# lab_1_demcheva_usb_rs232.net
KiCad netlist of a schematic drawn in Altium Designer
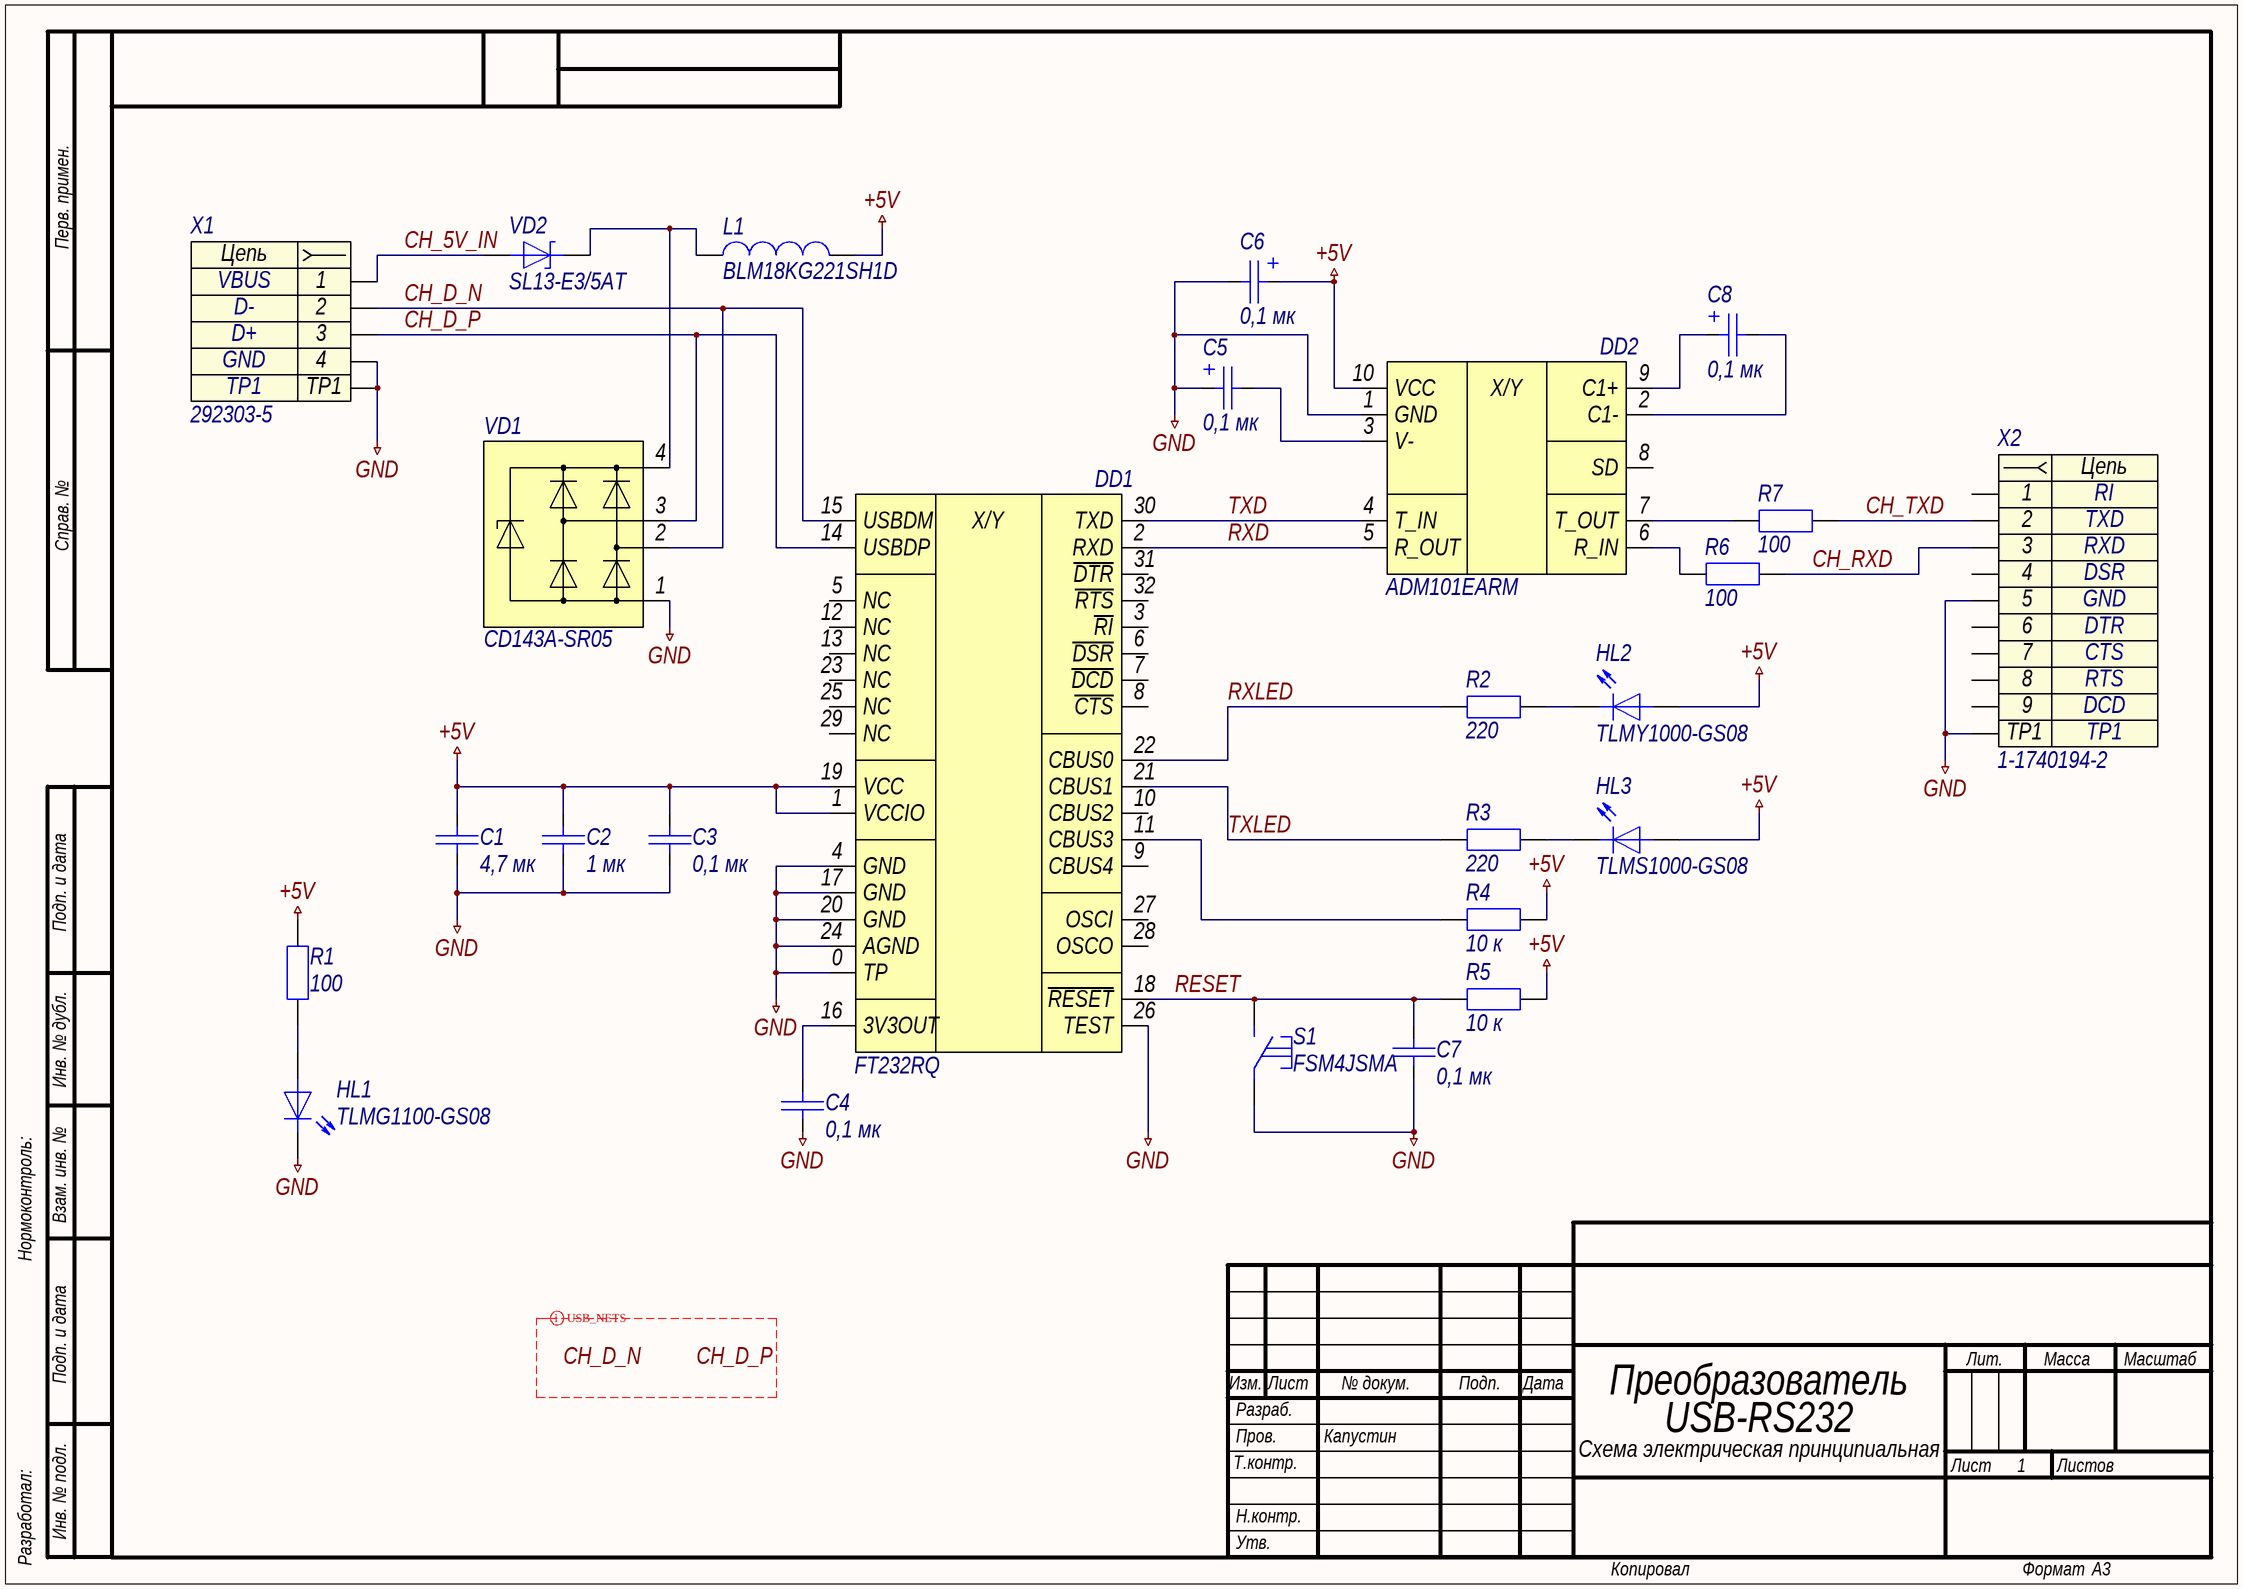
[diagram p0: lab_1_demcheva_usb_rs232.SchDoc]

(export (version "E")
  (design (tool "Eeschema 10.0.6"))
  (components
    (comp (ref "C1")
      (value "4,7 мк")
      (footprint "C0603")
      (description "=Описание")
      (libsource (lib "Database_Students") (part "C-NONPOLAR"))
    )
    (comp (ref "C2")
      (value "1 мк")
      (footprint "C0603")
      (description "=Описание")
      (libsource (lib "Database_Students") (part "C-NONPOLAR"))
    )
    (comp (ref "C3")
      (value "0,1 мк")
      (footprint "C0603")
      (description "=Описание")
      (libsource (lib "Database_Students") (part "C-NONPOLAR"))
    )
    (comp (ref "C4")
      (value "0,1 мк")
      (footprint "C0603")
      (description "=Описание")
      (libsource (lib "Database_Students") (part "C-NONPOLAR"))
    )
    (comp (ref "C5")
      (value "0,1 мк")
      (footprint "C1206POLAR")
      (description "=Описание")
      (libsource (lib "Database_Students") (part "C-POLAR"))
    )
    (comp (ref "C6")
      (value "0,1 мк")
      (footprint "C1206POLAR")
      (description "=Описание")
      (libsource (lib "Database_Students") (part "C-POLAR"))
    )
    (comp (ref "C7")
      (value "0,1 мк")
      (footprint "C0603")
      (description "=Описание")
      (libsource (lib "Database_Students") (part "C-NONPOLAR"))
    )
    (comp (ref "C8")
      (value "0,1 мк")
      (footprint "C1206POLAR")
      (description "=Описание")
      (libsource (lib "Database_Students") (part "C-POLAR"))
    )
    (comp (ref "DD1")
      (value "FT232RQ")
      (footprint "QFN-32-500x500x90")
      (description "=Описание")
      (libsource (lib "Database_Students") (part "FT232RQ"))
    )
    (comp (ref "DD2")
      (value "ADM101EARM")
      (footprint "MSOP-10")
      (description "=Описание")
      (libsource (lib "Database_Students") (part "ADM101EARM"))
    )
    (comp (ref "HL1")
      (value "TLMG1100-GS08")
      (footprint "HL0603")
      (description "=Описание")
      (libsource (lib "Database_Students") (part "HL-COMMON"))
    )
    (comp (ref "HL2")
      (value "TLMY1000-GS08")
      (footprint "HL0603")
      (description "=Описание")
      (libsource (lib "Database_Students") (part "HL-COMMON"))
    )
    (comp (ref "HL3")
      (value "TLMS1000-GS08")
      (footprint "HL0603")
      (description "=Описание")
      (libsource (lib "Database_Students") (part "HL-COMMON"))
    )
    (comp (ref "L1")
      (value "BLM18KG221SH1D")
      (footprint "BLM-2-0603")
      (description "=Описание")
      (libsource (lib "Database_Students") (part "FERRITE-BEAD"))
    )
    (comp (ref "R1")
      (value "100")
      (footprint "R0603")
      (description "=Описание")
      (libsource (lib "Database_Students") (part "R-COMMON"))
    )
    (comp (ref "R2")
      (value "220")
      (footprint "R0603")
      (description "=Описание")
      (libsource (lib "Database_Students") (part "R-COMMON"))
    )
    (comp (ref "R3")
      (value "220")
      (footprint "R0603")
      (description "=Описание")
      (libsource (lib "Database_Students") (part "R-COMMON"))
    )
    (comp (ref "R4")
      (value "10 к")
      (footprint "R0603")
      (description "=Описание")
      (libsource (lib "Database_Students") (part "R-COMMON"))
    )
    (comp (ref "R5")
      (value "10 к")
      (footprint "R0603")
      (description "=Описание")
      (libsource (lib "Database_Students") (part "R-COMMON"))
    )
    (comp (ref "R6")
      (value "100")
      (footprint "R0603")
      (description "=Описание")
      (libsource (lib "Database_Students") (part "R-COMMON"))
    )
    (comp (ref "R7")
      (value "100")
      (footprint "R0603")
      (description "=Описание")
      (libsource (lib "Database_Students") (part "R-COMMON"))
    )
    (comp (ref "S1")
      (value "FSM4JSMA")
      (footprint "FSM4JSMA")
      (description "=Описание")
      (libsource (lib "Database_Students") (part "SWITCH-01"))
    )
    (comp (ref "VD1")
      (value "CD143A-SR05")
      (footprint "SOT-143-4")
      (description "=Описание")
      (libsource (lib "Database_Students") (part "CD143A-SR05"))
    )
    (comp (ref "VD2")
      (value "SL13-E3/5AT")
      (footprint "DO-214AC")
      (description "=Описание")
      (libsource (lib "Database_Students") (part "DIODE-SCHOTTKY"))
    )
    (comp (ref "X1")
      (value "292303-5")
      (footprint "292303-5")
      (description "=Описание")
      (libsource (lib "Database_Students") (part "HEADER-4-TP1-SCT"))
    )
    (comp (ref "X2")
      (value "1-1740194-2")
      (footprint "1-1740194-2")
      (description "=Описание")
      (libsource (lib "Database_Students") (part "HEADER-9-TP1-SCT"))
    )
  )
  (nets
    (net (code "1") (name "+5V") (class "Default")
      (node (ref "C1") (pin "1") (pinfunction "1_1") (pintype "passive"))
      (node (ref "C2") (pin "1") (pinfunction "1_1") (pintype "passive"))
      (node (ref "C3") (pin "1") (pinfunction "1_1") (pintype "passive"))
      (node (ref "C6") (pin "1") (pinfunction "1_1") (pintype "passive"))
      (node (ref "DD1") (pin "1") (pinfunction "VCCIO_1") (pintype "passive"))
      (node (ref "DD1") (pin "19") (pinfunction "VCC_19") (pintype "passive"))
      (node (ref "DD2") (pin "10") (pinfunction "VCC_10") (pintype "passive"))
      (node (ref "HL2") (pin "2") (pinfunction "2_2") (pintype "passive"))
      (node (ref "HL3") (pin "2") (pinfunction "2_2") (pintype "passive"))
      (node (ref "L1") (pin "2") (pinfunction "2_2") (pintype "passive"))
      (node (ref "R1") (pin "2") (pinfunction "2_2") (pintype "passive"))
      (node (ref "R4") (pin "2") (pinfunction "2_2") (pintype "passive"))
      (node (ref "R5") (pin "2") (pinfunction "2_2") (pintype "passive"))
    )
    (net (code "2") (name "/CH_5V_IN") (class "Default")
      (node (ref "VD2") (pin "2") (pinfunction "2_2") (pintype "passive"))
      (node (ref "X1") (pin "1") (pinfunction "1_1") (pintype "passive"))
    )
    (net (code "3") (name "/CH_D_N") (class "Default")
      (node (ref "DD1") (pin "15") (pinfunction "USBDM_15") (pintype "passive"))
      (node (ref "VD1") (pin "2") (pinfunction "2_2") (pintype "passive"))
      (node (ref "X1") (pin "2") (pinfunction "2_2") (pintype "passive"))
    )
    (net (code "4") (name "/CH_D_P") (class "Default")
      (node (ref "DD1") (pin "14") (pinfunction "USBDP_14") (pintype "passive"))
      (node (ref "VD1") (pin "3") (pinfunction "3_3") (pintype "passive"))
      (node (ref "X1") (pin "3") (pinfunction "3_3") (pintype "passive"))
    )
    (net (code "5") (name "/CH_RXD") (class "Default")
      (node (ref "R6") (pin "2") (pinfunction "2_2") (pintype "passive"))
      (node (ref "X2") (pin "3") (pinfunction "3_3") (pintype "passive"))
    )
    (net (code "6") (name "/CH_TXD") (class "Default")
      (node (ref "R7") (pin "2") (pinfunction "2_2") (pintype "passive"))
      (node (ref "X2") (pin "2") (pinfunction "2_2") (pintype "passive"))
    )
    (net (code "7") (name "/RESET") (class "Default")
      (node (ref "C7") (pin "1") (pinfunction "1_1") (pintype "passive"))
      (node (ref "DD1") (pin "18") (pinfunction "~{RESET}_18") (pintype "passive"))
      (node (ref "R5") (pin "1") (pinfunction "1_1") (pintype "passive"))
      (node (ref "S1") (pin "2") (pinfunction "2_2") (pintype "passive"))
    )
    (net (code "8") (name "/RXD") (class "Default")
      (node (ref "DD1") (pin "2") (pinfunction "RXD_2") (pintype "passive"))
      (node (ref "DD2") (pin "5") (pinfunction "R_OUT_5") (pintype "passive"))
    )
    (net (code "9") (name "/RXLED") (class "Default")
      (node (ref "DD1") (pin "22") (pinfunction "CBUS0_22") (pintype "passive"))
      (node (ref "R2") (pin "1") (pinfunction "1_1") (pintype "passive"))
    )
    (net (code "10") (name "/TXD") (class "Default")
      (node (ref "DD1") (pin "30") (pinfunction "TXD_30") (pintype "passive"))
      (node (ref "DD2") (pin "4") (pinfunction "T_IN_4") (pintype "passive"))
    )
    (net (code "11") (name "/TXLED") (class "Default")
      (node (ref "DD1") (pin "21") (pinfunction "CBUS1_21") (pintype "passive"))
      (node (ref "R3") (pin "1") (pinfunction "1_1") (pintype "passive"))
    )
    (net (code "12") (name "GND") (class "Default")
      (node (ref "C1") (pin "2") (pinfunction "2_2") (pintype "passive"))
      (node (ref "C2") (pin "2") (pinfunction "2_2") (pintype "passive"))
      (node (ref "C3") (pin "2") (pinfunction "2_2") (pintype "passive"))
      (node (ref "C4") (pin "2") (pinfunction "2_2") (pintype "passive"))
      (node (ref "C5") (pin "1") (pinfunction "1_1") (pintype "passive"))
      (node (ref "C6") (pin "2") (pinfunction "2_2") (pintype "passive"))
      (node (ref "C7") (pin "2") (pinfunction "2_2") (pintype "passive"))
      (node (ref "DD1") (pin "0") (pinfunction "TP_0") (pintype "passive"))
      (node (ref "DD1") (pin "17") (pinfunction "GND_17") (pintype "passive"))
      (node (ref "DD1") (pin "20") (pinfunction "GND_20") (pintype "passive"))
      (node (ref "DD1") (pin "24") (pinfunction "AGND_24") (pintype "passive"))
      (node (ref "DD1") (pin "26") (pinfunction "TEST_26") (pintype "passive"))
      (node (ref "DD1") (pin "4") (pinfunction "GND_4") (pintype "passive"))
      (node (ref "DD2") (pin "1") (pinfunction "GND_1") (pintype "passive"))
      (node (ref "HL1") (pin "1") (pinfunction "1_1") (pintype "passive"))
      (node (ref "S1") (pin "1") (pinfunction "1_1") (pintype "passive"))
      (node (ref "VD1") (pin "1") (pinfunction "1_1") (pintype "passive"))
      (node (ref "X1") (pin "4") (pinfunction "4_4") (pintype "passive"))
      (node (ref "X1") (pin "TP1") (pinfunction "TP1_TP1") (pintype "passive"))
      (node (ref "X2") (pin "5") (pinfunction "5_5") (pintype "passive"))
      (node (ref "X2") (pin "TP1") (pinfunction "TP1_TP1") (pintype "passive"))
    )
    (net (code "13") (name "Net-(DD1-3V3OUT)") (class "Default")
      (node (ref "C4") (pin "1") (pinfunction "1_1") (pintype "passive"))
      (node (ref "DD1") (pin "16") (pinfunction "3V3OUT_16") (pintype "passive"))
    )
    (net (code "14") (name "Net-(DD1-CBUS3)") (class "Default")
      (node (ref "DD1") (pin "11") (pinfunction "CBUS3_11") (pintype "passive"))
      (node (ref "R4") (pin "1") (pinfunction "1_1") (pintype "passive"))
    )
    (net (code "15") (name "Net-(DD2-C1+)") (class "Default")
      (node (ref "C8") (pin "1") (pinfunction "1_1") (pintype "passive"))
      (node (ref "DD2") (pin "9") (pinfunction "C1+_9") (pintype "passive"))
    )
    (net (code "16") (name "Net-(DD2-C1-)") (class "Default")
      (node (ref "C8") (pin "2") (pinfunction "2_2") (pintype "passive"))
      (node (ref "DD2") (pin "2") (pinfunction "C1-_2") (pintype "passive"))
    )
    (net (code "17") (name "Net-(DD2-R_IN)") (class "Default")
      (node (ref "DD2") (pin "6") (pinfunction "R_IN_6") (pintype "passive"))
      (node (ref "R6") (pin "1") (pinfunction "1_1") (pintype "passive"))
    )
    (net (code "18") (name "Net-(DD2-T_OUT)") (class "Default")
      (node (ref "DD2") (pin "7") (pinfunction "T_OUT_7") (pintype "passive"))
      (node (ref "R7") (pin "1") (pinfunction "1_1") (pintype "passive"))
    )
    (net (code "19") (name "Net-(DD2-V-)") (class "Default")
      (node (ref "C5") (pin "2") (pinfunction "2_2") (pintype "passive"))
      (node (ref "DD2") (pin "3") (pinfunction "V-_3") (pintype "passive"))
    )
    (net (code "20") (name "Net-(HL1-Pad2)") (class "Default")
      (node (ref "HL1") (pin "2") (pinfunction "2_2") (pintype "passive"))
      (node (ref "R1") (pin "1") (pinfunction "1_1") (pintype "passive"))
    )
    (net (code "21") (name "Net-(HL2-Pad1)") (class "Default")
      (node (ref "HL2") (pin "1") (pinfunction "1_1") (pintype "passive"))
      (node (ref "R2") (pin "2") (pinfunction "2_2") (pintype "passive"))
    )
    (net (code "22") (name "Net-(HL3-Pad1)") (class "Default")
      (node (ref "HL3") (pin "1") (pinfunction "1_1") (pintype "passive"))
      (node (ref "R3") (pin "2") (pinfunction "2_2") (pintype "passive"))
    )
    (net (code "23") (name "Net-(L1-Pad1)") (class "Default")
      (node (ref "L1") (pin "1") (pinfunction "1_1") (pintype "passive"))
      (node (ref "VD1") (pin "4") (pinfunction "4_4") (pintype "passive"))
      (node (ref "VD2") (pin "1") (pinfunction "1_1") (pintype "passive"))
    )
    (net (code "24") (name "unconnected-(DD1-CBUS2-Pad10)") (class "Default")
      (node (ref "DD1") (pin "10") (pinfunction "CBUS2_10") (pintype "passive"))
    )
    (net (code "25") (name "unconnected-(DD1-CBUS4-Pad9)") (class "Default")
      (node (ref "DD1") (pin "9") (pinfunction "CBUS4_9") (pintype "passive"))
    )
    (net (code "26") (name "unconnected-(DD1-NC-Pad5)") (class "Default")
      (node (ref "DD1") (pin "5") (pinfunction "NC_5") (pintype "passive"))
    )
    (net (code "27") (name "unconnected-(DD1-NC-Pad12)") (class "Default")
      (node (ref "DD1") (pin "12") (pinfunction "NC_12") (pintype "passive"))
    )
    (net (code "28") (name "unconnected-(DD1-NC-Pad13)") (class "Default")
      (node (ref "DD1") (pin "13") (pinfunction "NC_13") (pintype "passive"))
    )
    (net (code "29") (name "unconnected-(DD1-NC-Pad23)") (class "Default")
      (node (ref "DD1") (pin "23") (pinfunction "NC_23") (pintype "passive"))
    )
    (net (code "30") (name "unconnected-(DD1-NC-Pad25)") (class "Default")
      (node (ref "DD1") (pin "25") (pinfunction "NC_25") (pintype "passive"))
    )
    (net (code "31") (name "unconnected-(DD1-NC-Pad29)") (class "Default")
      (node (ref "DD1") (pin "29") (pinfunction "NC_29") (pintype "passive"))
    )
    (net (code "32") (name "unconnected-(DD1-OSCI-Pad27)") (class "Default")
      (node (ref "DD1") (pin "27") (pinfunction "OSCI_27") (pintype "passive"))
    )
    (net (code "33") (name "unconnected-(DD1-OSCO-Pad28)") (class "Default")
      (node (ref "DD1") (pin "28") (pinfunction "OSCO_28") (pintype "passive"))
    )
    (net (code "34") (name "unconnected-(DD1-~{CTS}-Pad8)") (class "Default")
      (node (ref "DD1") (pin "8") (pinfunction "~{CTS}_8") (pintype "passive"))
    )
    (net (code "35") (name "unconnected-(DD1-~{DCD}-Pad7)") (class "Default")
      (node (ref "DD1") (pin "7") (pinfunction "~{DCD}_7") (pintype "passive"))
    )
    (net (code "36") (name "unconnected-(DD1-~{DSR}-Pad6)") (class "Default")
      (node (ref "DD1") (pin "6") (pinfunction "~{DSR}_6") (pintype "passive"))
    )
    (net (code "37") (name "unconnected-(DD1-~{DTR}-Pad31)") (class "Default")
      (node (ref "DD1") (pin "31") (pinfunction "~{DTR}_31") (pintype "passive"))
    )
    (net (code "38") (name "unconnected-(DD1-~{RI}-Pad3)") (class "Default")
      (node (ref "DD1") (pin "3") (pinfunction "~{RI}_3") (pintype "passive"))
    )
    (net (code "39") (name "unconnected-(DD1-~{RTS}-Pad32)") (class "Default")
      (node (ref "DD1") (pin "32") (pinfunction "~{RTS}_32") (pintype "passive"))
    )
    (net (code "40") (name "unconnected-(DD2-SD-Pad8)") (class "Default")
      (node (ref "DD2") (pin "8") (pinfunction "SD_8") (pintype "passive"))
    )
    (net (code "41") (name "unconnected-(X2-Pad1)") (class "Default")
      (node (ref "X2") (pin "1") (pinfunction "1_1") (pintype "passive"))
    )
    (net (code "42") (name "unconnected-(X2-Pad4)") (class "Default")
      (node (ref "X2") (pin "4") (pinfunction "4_4") (pintype "passive"))
    )
    (net (code "43") (name "unconnected-(X2-Pad6)") (class "Default")
      (node (ref "X2") (pin "6") (pinfunction "6_6") (pintype "passive"))
    )
    (net (code "44") (name "unconnected-(X2-Pad7)") (class "Default")
      (node (ref "X2") (pin "7") (pinfunction "7_7") (pintype "passive"))
    )
    (net (code "45") (name "unconnected-(X2-Pad8)") (class "Default")
      (node (ref "X2") (pin "8") (pinfunction "8_8") (pintype "passive"))
    )
    (net (code "46") (name "unconnected-(X2-Pad9)") (class "Default")
      (node (ref "X2") (pin "9") (pinfunction "9_9") (pintype "passive"))
    )
  )
)
